# main_3_0.net
KiCad netlist of a schematic drawn in EAGLE
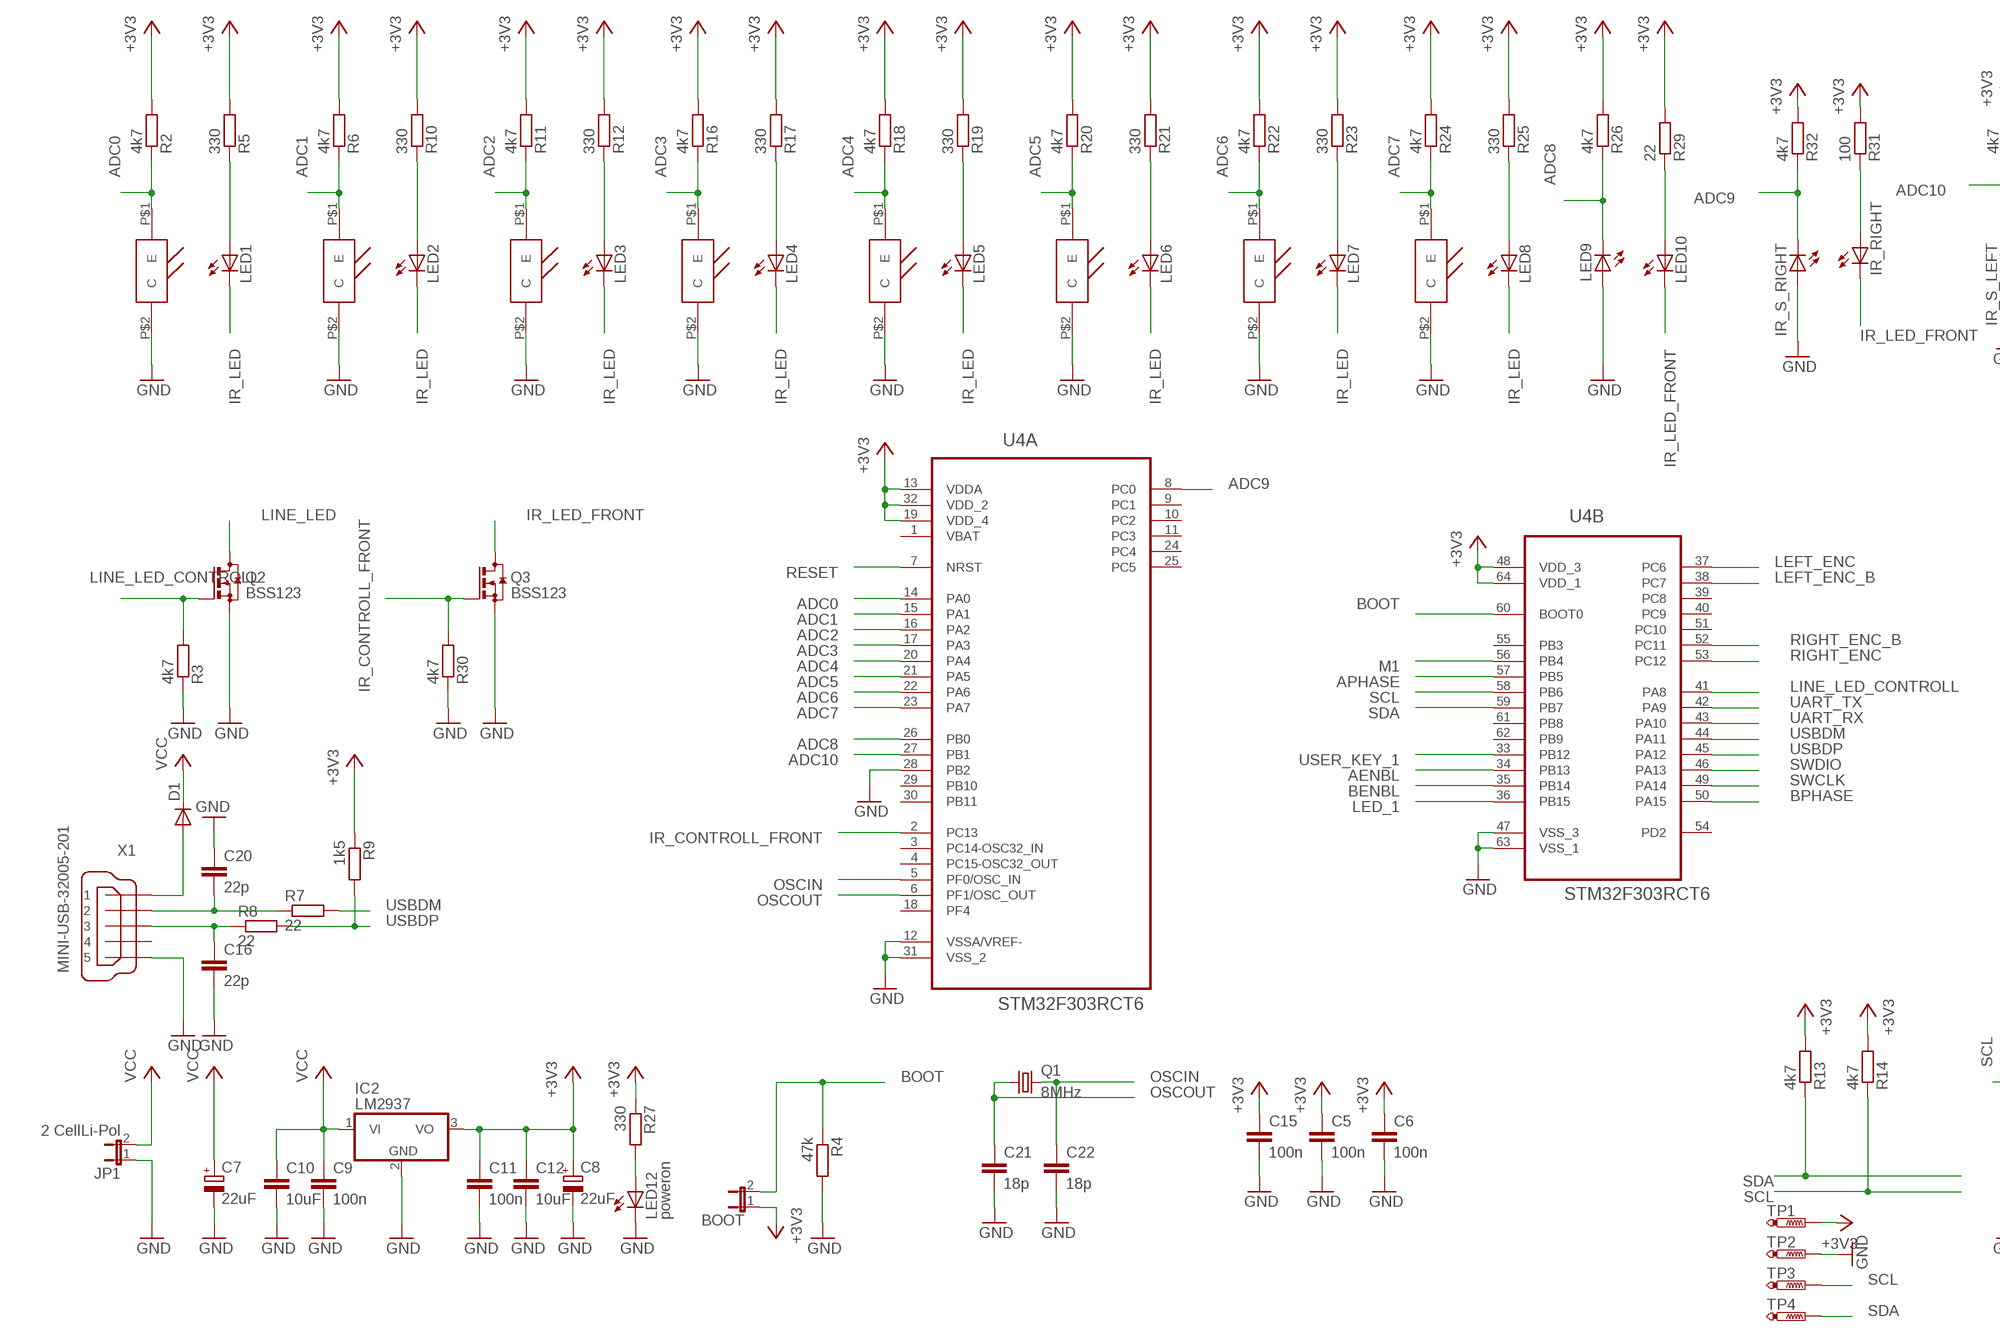
[diagram p0: schematic, sheet 1, part 1 of 2]
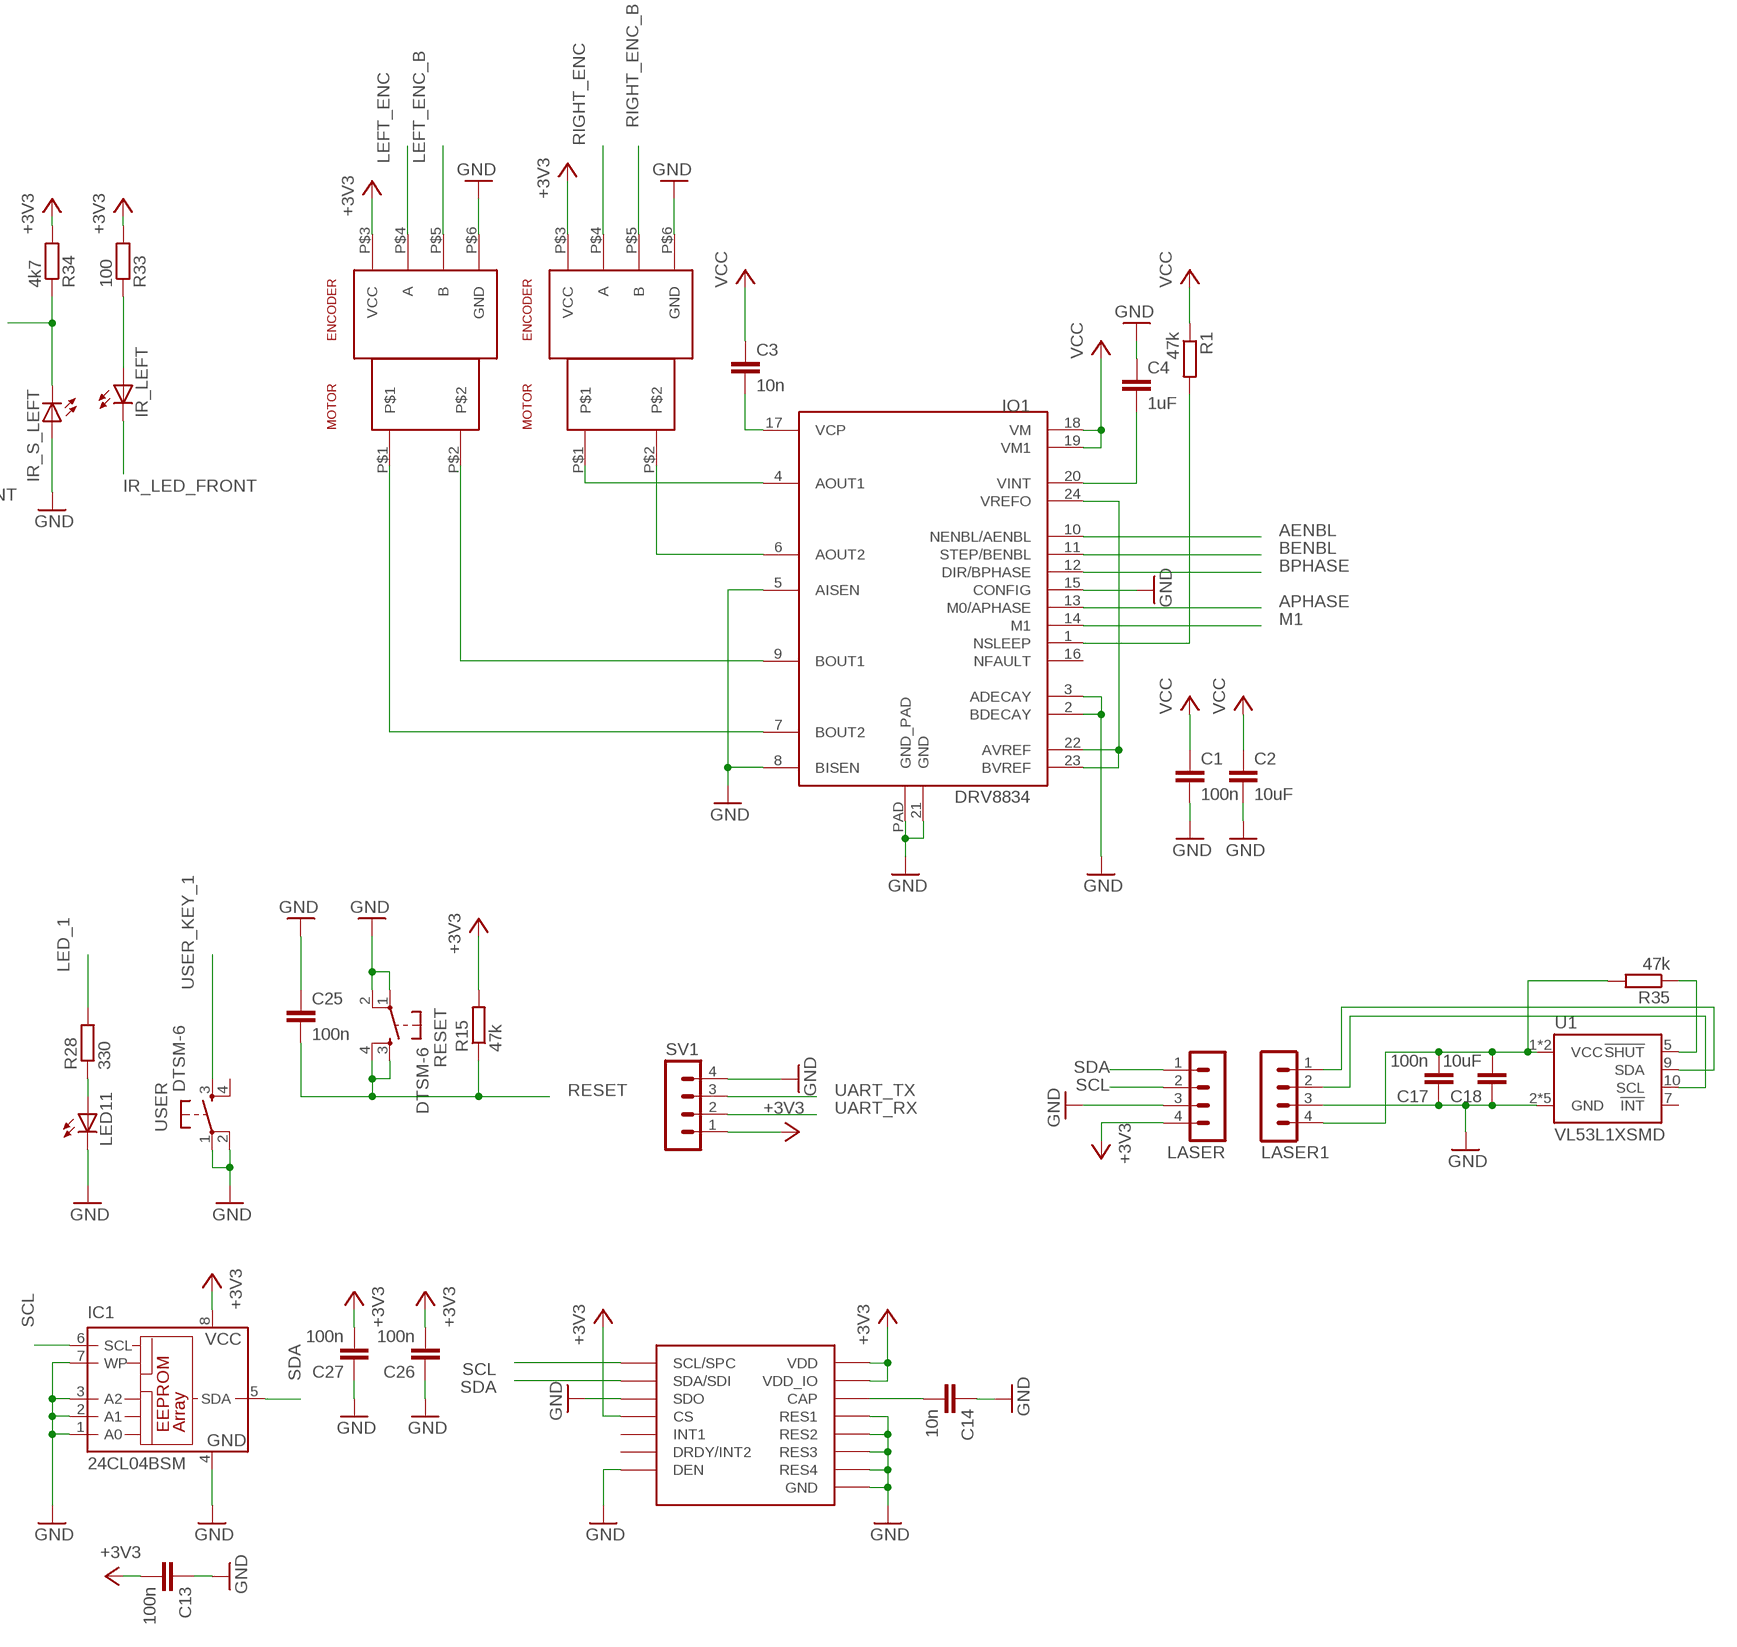
[diagram p1: schematic, sheet 1, part 2 of 2]

(export (version "E")
  (design (tool "Eeschema 10.0.6"))
  (components
    (comp (ref "BOOT")
      (value "JP1E")
      (footprint "eagle-import:JP1")
      (libsource (lib "eagle-import") (part "JP1E"))
    )
    (comp (ref "C1")
      (value "100n")
      (footprint "eagle-import:C1206")
      (libsource (lib "eagle-import") (part "C-EUC1206"))
    )
    (comp (ref "C2")
      (value "10uF")
      (footprint "eagle-import:C1206")
      (libsource (lib "eagle-import") (part "C-EUC1206"))
    )
    (comp (ref "C3")
      (value "10n")
      (footprint "eagle-import:C1206")
      (libsource (lib "eagle-import") (part "C-EUC1206"))
    )
    (comp (ref "C4")
      (value "1uF")
      (footprint "eagle-import:C1206")
      (libsource (lib "eagle-import") (part "C-EUC1206"))
    )
    (comp (ref "C5")
      (value "100n")
      (footprint "eagle-import:C0805")
      (libsource (lib "eagle-import") (part "C-EUC0805"))
    )
    (comp (ref "C6")
      (value "100n")
      (footprint "eagle-import:C0805")
      (libsource (lib "eagle-import") (part "C-EUC0805"))
    )
    (comp (ref "C7")
      (value "22uF")
      (footprint "eagle-import:153CLV-0505")
      (libsource (lib "eagle-import") (part "CPOL-EU153CLV-0505"))
    )
    (comp (ref "C8")
      (value "22uF")
      (footprint "eagle-import:153CLV-0505")
      (libsource (lib "eagle-import") (part "CPOL-EU153CLV-0505"))
    )
    (comp (ref "C9")
      (value "100n")
      (footprint "eagle-import:C0805")
      (libsource (lib "eagle-import") (part "C-EUC0805"))
    )
    (comp (ref "C10")
      (value "10uF")
      (footprint "eagle-import:C0805")
      (libsource (lib "eagle-import") (part "C-EUC0805"))
    )
    (comp (ref "C11")
      (value "100n")
      (footprint "eagle-import:C0805")
      (libsource (lib "eagle-import") (part "C-EUC0805"))
    )
    (comp (ref "C12")
      (value "10uF")
      (footprint "eagle-import:C0805")
      (libsource (lib "eagle-import") (part "C-EUC0805"))
    )
    (comp (ref "C13")
      (value "100n")
      (footprint "eagle-import:C0805")
      (libsource (lib "eagle-import") (part "C-EUC0805"))
    )
    (comp (ref "C14")
      (value "10n")
      (footprint "eagle-import:C0805")
      (libsource (lib "eagle-import") (part "C-EUC0805"))
    )
    (comp (ref "C15")
      (value "100n")
      (footprint "eagle-import:C0805")
      (libsource (lib "eagle-import") (part "C-EUC0805"))
    )
    (comp (ref "C16")
      (value "22p")
      (footprint "eagle-import:C0805")
      (libsource (lib "eagle-import") (part "C-EUC0805"))
    )
    (comp (ref "C17")
      (value "100n")
      (footprint "eagle-import:C0805")
      (libsource (lib "eagle-import") (part "C-EUC0805"))
    )
    (comp (ref "C18")
      (value "10uF")
      (footprint "eagle-import:C0805")
      (libsource (lib "eagle-import") (part "C-EUC0805"))
    )
    (comp (ref "C20")
      (value "22p")
      (footprint "eagle-import:C0805")
      (libsource (lib "eagle-import") (part "C-EUC0805"))
    )
    (comp (ref "C21")
      (value "18p")
      (footprint "eagle-import:C0805")
      (libsource (lib "eagle-import") (part "C-EUC0805"))
    )
    (comp (ref "C22")
      (value "18p")
      (footprint "eagle-import:C0805")
      (libsource (lib "eagle-import") (part "C-EUC0805"))
    )
    (comp (ref "C25")
      (value "100n")
      (footprint "eagle-import:C0805")
      (libsource (lib "eagle-import") (part "C-EUC0805"))
    )
    (comp (ref "C26")
      (value "100n")
      (footprint "eagle-import:C0805")
      (libsource (lib "eagle-import") (part "C-EUC0805"))
    )
    (comp (ref "C27")
      (value "100n")
      (footprint "eagle-import:C0805")
      (libsource (lib "eagle-import") (part "C-EUC0805"))
    )
    (comp (ref "D1")
      (value "DIODE-SMB")
      (footprint "eagle-import:SMB")
      (libsource (lib "eagle-import") (part "DIODE-SMB"))
    )
    (comp (ref "IC1")
      (value "24CL04BSM")
      (footprint "eagle-import:SO-08M")
      (fields (field (name "MPN") "FM24CL04-S"))
      (libsource (lib "eagle-import") (part "24SMCL04B"))
    )
    (comp (ref "IC2")
      (value "LM2937")
      (footprint "eagle-import:TO263-3")
      (libsource (lib "eagle-import") (part "LM2937"))
    )
    (comp (ref "IO1")
      (value "DRV8834")
      (footprint "eagle-import:DRV8834_PCK")
      (libsource (lib "eagle-import") (part "DRV8834"))
    )
    (comp (ref "IR_LEFT")
      (value "LED5MM")
      (footprint "eagle-import:LED5MM")
      (libsource (lib "eagle-import") (part "my_parts_LED5MM"))
    )
    (comp (ref "IR_RIGHT")
      (value "LED5MM")
      (footprint "eagle-import:LED5MM")
      (libsource (lib "eagle-import") (part "my_parts_LED5MM"))
    )
    (comp (ref "IR_S_LEFT")
      (value "LED5MM")
      (footprint "eagle-import:LED5MM")
      (libsource (lib "eagle-import") (part "my_parts_LED5MM"))
    )
    (comp (ref "IR_S_RIGHT")
      (value "LED5MM")
      (footprint "eagle-import:LED5MM")
      (libsource (lib "eagle-import") (part "my_parts_LED5MM"))
    )
    (comp (ref "JP1")
      (value "2 CellLi-Pol")
      (footprint "eagle-import:JP1")
      (libsource (lib "eagle-import") (part "JP1E"))
    )
    (comp (ref "LASER")
      (value "MA04-1")
      (footprint "eagle-import:MA04-1")
      (libsource (lib "eagle-import") (part "MA04-1"))
    )
    (comp (ref "LASER1")
      (value "MA04-1")
      (footprint "eagle-import:MA04-1")
      (libsource (lib "eagle-import") (part "MA04-1"))
    )
    (comp (ref "LED1")
      (value "LEDCHIPLED_1206")
      (footprint "eagle-import:CHIPLED_1206")
      (libsource (lib "eagle-import") (part "LEDCHIPLED_1206"))
    )
    (comp (ref "LED2")
      (value "LEDCHIPLED_1206")
      (footprint "eagle-import:CHIPLED_1206")
      (libsource (lib "eagle-import") (part "LEDCHIPLED_1206"))
    )
    (comp (ref "LED3")
      (value "LEDCHIPLED_1206")
      (footprint "eagle-import:CHIPLED_1206")
      (libsource (lib "eagle-import") (part "LEDCHIPLED_1206"))
    )
    (comp (ref "LED4")
      (value "LEDCHIPLED_1206")
      (footprint "eagle-import:CHIPLED_1206")
      (libsource (lib "eagle-import") (part "LEDCHIPLED_1206"))
    )
    (comp (ref "LED5")
      (value "LEDCHIPLED_1206")
      (footprint "eagle-import:CHIPLED_1206")
      (libsource (lib "eagle-import") (part "LEDCHIPLED_1206"))
    )
    (comp (ref "LED6")
      (value "LEDCHIPLED_1206")
      (footprint "eagle-import:CHIPLED_1206")
      (libsource (lib "eagle-import") (part "LEDCHIPLED_1206"))
    )
    (comp (ref "LED7")
      (value "LEDCHIPLED_1206")
      (footprint "eagle-import:CHIPLED_1206")
      (libsource (lib "eagle-import") (part "LEDCHIPLED_1206"))
    )
    (comp (ref "LED8")
      (value "LEDCHIPLED_1206")
      (footprint "eagle-import:CHIPLED_1206")
      (libsource (lib "eagle-import") (part "LEDCHIPLED_1206"))
    )
    (comp (ref "LED9")
      (value "LED5MM")
      (footprint "eagle-import:LED5MM")
      (libsource (lib "eagle-import") (part "my_parts_LED5MM"))
    )
    (comp (ref "LED10")
      (value "LED5MM")
      (footprint "eagle-import:LED5MM")
      (libsource (lib "eagle-import") (part "my_parts_LED5MM"))
    )
    (comp (ref "LED11")
      (value "LEDCHIPLED_1206")
      (footprint "eagle-import:CHIPLED_1206")
      (libsource (lib "eagle-import") (part "LEDCHIPLED_1206"))
    )
    (comp (ref "LED12")
      (value "poweron")
      (footprint "eagle-import:CHIPLED_1206")
      (libsource (lib "eagle-import") (part "LEDCHIPLED_1206"))
    )
    (comp (ref "LSM6DS0")
      (value "L3GD20H")
      (footprint "eagle-import:LGA16L")
      (libsource (lib "eagle-import") (part "L3GD20H"))
    )
    (comp (ref "Q1")
      (value "8MHz")
      (footprint "eagle-import:CTS406")
      (libsource (lib "eagle-import") (part "CRYSTALCTS406"))
    )
    (comp (ref "Q2")
      (value "BSS123")
      (footprint "eagle-import:SOT23")
      (libsource (lib "eagle-import") (part "BSS123"))
    )
    (comp (ref "Q3")
      (value "BSS123")
      (footprint "eagle-import:SOT23")
      (libsource (lib "eagle-import") (part "BSS123"))
    )
    (comp (ref "R1")
      (value "47k")
      (footprint "eagle-import:M1206")
      (libsource (lib "eagle-import") (part "R-EU_M1206"))
    )
    (comp (ref "R2")
      (value "4k7")
      (footprint "eagle-import:M0805")
      (libsource (lib "eagle-import") (part "R-EU_M0805"))
    )
    (comp (ref "R3")
      (value "4k7")
      (footprint "eagle-import:M0805")
      (libsource (lib "eagle-import") (part "R-EU_M0805"))
    )
    (comp (ref "R4")
      (value "47k")
      (footprint "eagle-import:M0805")
      (libsource (lib "eagle-import") (part "R-EU_M0805"))
    )
    (comp (ref "R5")
      (value "330")
      (footprint "eagle-import:M0805")
      (libsource (lib "eagle-import") (part "R-EU_M0805"))
    )
    (comp (ref "R6")
      (value "4k7")
      (footprint "eagle-import:M0805")
      (libsource (lib "eagle-import") (part "R-EU_M0805"))
    )
    (comp (ref "R7")
      (value "22")
      (footprint "eagle-import:M0805")
      (libsource (lib "eagle-import") (part "R-EU_M0805"))
    )
    (comp (ref "R8")
      (value "22")
      (footprint "eagle-import:M0805")
      (libsource (lib "eagle-import") (part "R-EU_M0805"))
    )
    (comp (ref "R9")
      (value "1k5")
      (footprint "eagle-import:M0805")
      (libsource (lib "eagle-import") (part "R-EU_M0805"))
    )
    (comp (ref "R10")
      (value "330")
      (footprint "eagle-import:M0805")
      (libsource (lib "eagle-import") (part "R-EU_M0805"))
    )
    (comp (ref "R11")
      (value "4k7")
      (footprint "eagle-import:M0805")
      (libsource (lib "eagle-import") (part "R-EU_M0805"))
    )
    (comp (ref "R12")
      (value "330")
      (footprint "eagle-import:M0805")
      (libsource (lib "eagle-import") (part "R-EU_M0805"))
    )
    (comp (ref "R13")
      (value "4k7")
      (footprint "eagle-import:M0805")
      (libsource (lib "eagle-import") (part "R-EU_M0805"))
    )
    (comp (ref "R14")
      (value "4k7")
      (footprint "eagle-import:M0805")
      (libsource (lib "eagle-import") (part "R-EU_M0805"))
    )
    (comp (ref "R15")
      (value "47k")
      (footprint "eagle-import:M0805")
      (libsource (lib "eagle-import") (part "R-EU_M0805"))
    )
    (comp (ref "R16")
      (value "4k7")
      (footprint "eagle-import:M0805")
      (libsource (lib "eagle-import") (part "R-EU_M0805"))
    )
    (comp (ref "R17")
      (value "330")
      (footprint "eagle-import:M0805")
      (libsource (lib "eagle-import") (part "R-EU_M0805"))
    )
    (comp (ref "R18")
      (value "4k7")
      (footprint "eagle-import:M0805")
      (libsource (lib "eagle-import") (part "R-EU_M0805"))
    )
    (comp (ref "R19")
      (value "330")
      (footprint "eagle-import:M0805")
      (libsource (lib "eagle-import") (part "R-EU_M0805"))
    )
    (comp (ref "R20")
      (value "4k7")
      (footprint "eagle-import:M0805")
      (libsource (lib "eagle-import") (part "R-EU_M0805"))
    )
    (comp (ref "R21")
      (value "330")
      (footprint "eagle-import:M0805")
      (libsource (lib "eagle-import") (part "R-EU_M0805"))
    )
    (comp (ref "R22")
      (value "4k7")
      (footprint "eagle-import:M0805")
      (libsource (lib "eagle-import") (part "R-EU_M0805"))
    )
    (comp (ref "R23")
      (value "330")
      (footprint "eagle-import:M0805")
      (libsource (lib "eagle-import") (part "R-EU_M0805"))
    )
    (comp (ref "R24")
      (value "4k7")
      (footprint "eagle-import:M0805")
      (libsource (lib "eagle-import") (part "R-EU_M0805"))
    )
    (comp (ref "R25")
      (value "330")
      (footprint "eagle-import:M0805")
      (libsource (lib "eagle-import") (part "R-EU_M0805"))
    )
    (comp (ref "R26")
      (value "4k7")
      (footprint "eagle-import:M0805")
      (libsource (lib "eagle-import") (part "R-EU_M0805"))
    )
    (comp (ref "R27")
      (value "330")
      (footprint "eagle-import:M0805")
      (libsource (lib "eagle-import") (part "R-EU_M0805"))
    )
    (comp (ref "R28")
      (value "330")
      (footprint "eagle-import:M0805")
      (libsource (lib "eagle-import") (part "R-EU_M0805"))
    )
    (comp (ref "R29")
      (value "22")
      (footprint "eagle-import:M0805")
      (libsource (lib "eagle-import") (part "R-EU_M0805"))
    )
    (comp (ref "R30")
      (value "4k7")
      (footprint "eagle-import:M0805")
      (libsource (lib "eagle-import") (part "R-EU_M0805"))
    )
    (comp (ref "R31")
      (value "100")
      (footprint "eagle-import:M0805")
      (libsource (lib "eagle-import") (part "R-EU_M0805"))
    )
    (comp (ref "R32")
      (value "4k7")
      (footprint "eagle-import:M0805")
      (libsource (lib "eagle-import") (part "R-EU_M0805"))
    )
    (comp (ref "R33")
      (value "100")
      (footprint "eagle-import:M0805")
      (libsource (lib "eagle-import") (part "R-EU_M0805"))
    )
    (comp (ref "R34")
      (value "4k7")
      (footprint "eagle-import:M0805")
      (libsource (lib "eagle-import") (part "R-EU_M0805"))
    )
    (comp (ref "R35")
      (value "47k")
      (footprint "eagle-import:M0805")
      (libsource (lib "eagle-import") (part "R-EU_M0805"))
    )
    (comp (ref "RESET")
      (value "DTSM-6")
      (footprint "eagle-import:DTSM-6")
      (libsource (lib "eagle-import") (part "DTSM-6"))
    )
    (comp (ref "SV1")
      (value "MA04-1")
      (footprint "eagle-import:MA04-1")
      (libsource (lib "eagle-import") (part "MA04-1"))
    )
    (comp (ref "TP1")
      (value "PTR1B1,27")
      (footprint "eagle-import:B1,27")
      (libsource (lib "eagle-import") (part "PTR1B1,27"))
    )
    (comp (ref "TP2")
      (value "PTR1B1,27")
      (footprint "eagle-import:B1,27")
      (libsource (lib "eagle-import") (part "PTR1B1,27"))
    )
    (comp (ref "TP3")
      (value "PTR1B1,27")
      (footprint "eagle-import:B1,27")
      (libsource (lib "eagle-import") (part "PTR1B1,27"))
    )
    (comp (ref "TP4")
      (value "PTR1B1,27")
      (footprint "eagle-import:B1,27")
      (libsource (lib "eagle-import") (part "PTR1B1,27"))
    )
    (comp (ref "U$3")
      (value "SFH3710")
      (footprint "eagle-import:SFH3710")
      (libsource (lib "eagle-import") (part "SFH3710"))
    )
    (comp (ref "U$4")
      (value "SFH3710")
      (footprint "eagle-import:SFH3710")
      (libsource (lib "eagle-import") (part "SFH3710"))
    )
    (comp (ref "U$5")
      (value "SFH3710")
      (footprint "eagle-import:SFH3710")
      (libsource (lib "eagle-import") (part "SFH3710"))
    )
    (comp (ref "U$6")
      (value "SFH3710")
      (footprint "eagle-import:SFH3710")
      (libsource (lib "eagle-import") (part "SFH3710"))
    )
    (comp (ref "U$7")
      (value "SFH3710")
      (footprint "eagle-import:SFH3710")
      (libsource (lib "eagle-import") (part "SFH3710"))
    )
    (comp (ref "U$8")
      (value "SFH3710")
      (footprint "eagle-import:SFH3710")
      (libsource (lib "eagle-import") (part "SFH3710"))
    )
    (comp (ref "U$9")
      (value "SFH3710")
      (footprint "eagle-import:SFH3710")
      (libsource (lib "eagle-import") (part "SFH3710"))
    )
    (comp (ref "U$10")
      (value "SFH3710")
      (footprint "eagle-import:SFH3710")
      (libsource (lib "eagle-import") (part "SFH3710"))
    )
    (comp (ref "U$11")
      (value "POLOLU_GEAR_MOTORPOLO")
      (footprint "eagle-import:POLOLU_GEAR_MOTOR")
      (libsource (lib "eagle-import") (part "POLOLU_GEAR_MOTORPOLO"))
    )
    (comp (ref "U$12")
      (value "POLOLU_GEAR_MOTORPOLO")
      (footprint "eagle-import:POLOLU_GEAR_MOTOR")
      (libsource (lib "eagle-import") (part "POLOLU_GEAR_MOTORPOLO"))
    )
    (comp (ref "U1")
      (value "VL53L1XSMD")
      (footprint "eagle-import:VL53L1X")
      (libsource (lib "eagle-import") (part "VL53L1XSMD"))
    )
    (comp (ref "U4")
      (value "STM32F303RCT6")
      (footprint "eagle-import:QFP50P1200X1200X160-64N")
      (libsource (lib "eagle-import") (part "STM32F303RCT6"))
    )
    (comp (ref "USER")
      (value "DTSM-6")
      (footprint "eagle-import:DTSM-6")
      (libsource (lib "eagle-import") (part "DTSM-6"))
    )
    (comp (ref "X1")
      (value "MINI-USB-32005-201")
      (footprint "eagle-import:32005-201")
      (libsource (lib "eagle-import") (part "MINI-USB-32005-201"))
    )
  )
  (nets
    (net (code "1") (name "+3V3") (class "Default")
      (node (ref "BOOT") (pin "1") (pinfunction "1_1") (pintype "passive"))
      (node (ref "C11") (pin "1") (pinfunction "1_1") (pintype "passive"))
      (node (ref "C12") (pin "1") (pinfunction "1_1") (pintype "passive"))
      (node (ref "C13") (pin "2") (pinfunction "2_2") (pintype "passive"))
      (node (ref "C15") (pin "1") (pinfunction "1_1") (pintype "passive"))
      (node (ref "C26") (pin "2") (pinfunction "2_2") (pintype "passive"))
      (node (ref "C27") (pin "2") (pinfunction "2_2") (pintype "passive"))
      (node (ref "C5") (pin "1") (pinfunction "1_1") (pintype "passive"))
      (node (ref "C6") (pin "1") (pinfunction "1_1") (pintype "passive"))
      (node (ref "C8") (pin "+") (pinfunction "+_+") (pintype "passive"))
      (node (ref "IC1") (pin "8") (pinfunction "VCC_8") (pintype "power_in"))
      (node (ref "IC2") (pin "3") (pinfunction "VO_3") (pintype "passive"))
      (node (ref "LASER") (pin "4") (pinfunction "4_4") (pintype "passive"))
      (node (ref "LSM6DS0") (pin "P$1") (pinfunction "VDD_IO_P$1") (pintype "power_in"))
      (node (ref "LSM6DS0") (pin "P$16") (pinfunction "VDD_P$16") (pintype "power_in"))
      (node (ref "LSM6DS0") (pin "P$5") (pinfunction "CS_P$5") (pintype "bidirectional"))
      (node (ref "R10") (pin "2") (pinfunction "2_2") (pintype "passive"))
      (node (ref "R11") (pin "2") (pinfunction "2_2") (pintype "passive"))
      (node (ref "R12") (pin "2") (pinfunction "2_2") (pintype "passive"))
      (node (ref "R13") (pin "2") (pinfunction "2_2") (pintype "passive"))
      (node (ref "R14") (pin "2") (pinfunction "2_2") (pintype "passive"))
      (node (ref "R15") (pin "2") (pinfunction "2_2") (pintype "passive"))
      (node (ref "R16") (pin "2") (pinfunction "2_2") (pintype "passive"))
      (node (ref "R17") (pin "2") (pinfunction "2_2") (pintype "passive"))
      (node (ref "R18") (pin "2") (pinfunction "2_2") (pintype "passive"))
      (node (ref "R19") (pin "2") (pinfunction "2_2") (pintype "passive"))
      (node (ref "R2") (pin "2") (pinfunction "2_2") (pintype "passive"))
      (node (ref "R20") (pin "2") (pinfunction "2_2") (pintype "passive"))
      (node (ref "R21") (pin "2") (pinfunction "2_2") (pintype "passive"))
      (node (ref "R22") (pin "2") (pinfunction "2_2") (pintype "passive"))
      (node (ref "R23") (pin "2") (pinfunction "2_2") (pintype "passive"))
      (node (ref "R24") (pin "2") (pinfunction "2_2") (pintype "passive"))
      (node (ref "R25") (pin "2") (pinfunction "2_2") (pintype "passive"))
      (node (ref "R26") (pin "2") (pinfunction "2_2") (pintype "passive"))
      (node (ref "R27") (pin "1") (pinfunction "1_1") (pintype "passive"))
      (node (ref "R29") (pin "2") (pinfunction "2_2") (pintype "passive"))
      (node (ref "R31") (pin "2") (pinfunction "2_2") (pintype "passive"))
      (node (ref "R32") (pin "2") (pinfunction "2_2") (pintype "passive"))
      (node (ref "R33") (pin "2") (pinfunction "2_2") (pintype "passive"))
      (node (ref "R34") (pin "2") (pinfunction "2_2") (pintype "passive"))
      (node (ref "R5") (pin "2") (pinfunction "2_2") (pintype "passive"))
      (node (ref "R6") (pin "2") (pinfunction "2_2") (pintype "passive"))
      (node (ref "R9") (pin "1") (pinfunction "1_1") (pintype "passive"))
      (node (ref "SV1") (pin "1") (pinfunction "1_1") (pintype "passive"))
      (node (ref "TP1") (pin "TP") (pinfunction "TP_TP") (pintype "input"))
      (node (ref "U$11") (pin "P$3") (pinfunction "VCC_P$3") (pintype "bidirectional"))
      (node (ref "U$12") (pin "P$3") (pinfunction "VCC_P$3") (pintype "bidirectional"))
      (node (ref "U4") (pin "13") (pinfunction "VDDA_13") (pintype "power_in"))
      (node (ref "U4") (pin "19") (pinfunction "VDD_4_19") (pintype "power_in"))
      (node (ref "U4") (pin "32") (pinfunction "VDD_2_32") (pintype "power_in"))
      (node (ref "U4") (pin "48") (pinfunction "VDD_3_48") (pintype "power_in"))
      (node (ref "U4") (pin "64") (pinfunction "VDD_1_64") (pintype "power_in"))
    )
    (net (code "2") (name "/ADC0") (class "Default")
      (node (ref "R2") (pin "1") (pinfunction "1_1") (pintype "passive"))
      (node (ref "U$3") (pin "P$1") (pinfunction "E_P$1") (pintype "bidirectional"))
      (node (ref "U4") (pin "14") (pinfunction "PA0_14") (pintype "bidirectional"))
    )
    (net (code "3") (name "/ADC1") (class "Default")
      (node (ref "R6") (pin "1") (pinfunction "1_1") (pintype "passive"))
      (node (ref "U$4") (pin "P$1") (pinfunction "E_P$1") (pintype "bidirectional"))
      (node (ref "U4") (pin "15") (pinfunction "PA1_15") (pintype "bidirectional"))
    )
    (net (code "4") (name "/ADC2") (class "Default")
      (node (ref "R11") (pin "1") (pinfunction "1_1") (pintype "passive"))
      (node (ref "U$5") (pin "P$1") (pinfunction "E_P$1") (pintype "bidirectional"))
      (node (ref "U4") (pin "16") (pinfunction "PA2_16") (pintype "bidirectional"))
    )
    (net (code "5") (name "/ADC3") (class "Default")
      (node (ref "R16") (pin "1") (pinfunction "1_1") (pintype "passive"))
      (node (ref "U$6") (pin "P$1") (pinfunction "E_P$1") (pintype "bidirectional"))
      (node (ref "U4") (pin "17") (pinfunction "PA3_17") (pintype "bidirectional"))
    )
    (net (code "6") (name "/ADC4") (class "Default")
      (node (ref "R18") (pin "1") (pinfunction "1_1") (pintype "passive"))
      (node (ref "U$7") (pin "P$1") (pinfunction "E_P$1") (pintype "bidirectional"))
      (node (ref "U4") (pin "20") (pinfunction "PA4_20") (pintype "bidirectional"))
    )
    (net (code "7") (name "/ADC5") (class "Default")
      (node (ref "R20") (pin "1") (pinfunction "1_1") (pintype "passive"))
      (node (ref "U$8") (pin "P$1") (pinfunction "E_P$1") (pintype "bidirectional"))
      (node (ref "U4") (pin "21") (pinfunction "PA5_21") (pintype "bidirectional"))
    )
    (net (code "8") (name "/ADC6") (class "Default")
      (node (ref "R22") (pin "1") (pinfunction "1_1") (pintype "passive"))
      (node (ref "U$9") (pin "P$1") (pinfunction "E_P$1") (pintype "bidirectional"))
      (node (ref "U4") (pin "22") (pinfunction "PA6_22") (pintype "bidirectional"))
    )
    (net (code "9") (name "/ADC7") (class "Default")
      (node (ref "R24") (pin "1") (pinfunction "1_1") (pintype "passive"))
      (node (ref "U$10") (pin "P$1") (pinfunction "E_P$1") (pintype "bidirectional"))
      (node (ref "U4") (pin "23") (pinfunction "PA7_23") (pintype "bidirectional"))
    )
    (net (code "10") (name "/ADC8") (class "Default")
      (node (ref "LED9") (pin "K") (pinfunction "C_K") (pintype "passive"))
      (node (ref "R26") (pin "1") (pinfunction "1_1") (pintype "passive"))
      (node (ref "U4") (pin "26") (pinfunction "PB0_26") (pintype "bidirectional"))
    )
    (net (code "11") (name "/ADC9") (class "Default")
      (node (ref "IR_S_RIGHT") (pin "K") (pinfunction "C_K") (pintype "passive"))
      (node (ref "R32") (pin "1") (pinfunction "1_1") (pintype "passive"))
      (node (ref "U4") (pin "8") (pinfunction "PC0_8") (pintype "bidirectional"))
    )
    (net (code "12") (name "/ADC10") (class "Default")
      (node (ref "IR_S_LEFT") (pin "K") (pinfunction "C_K") (pintype "passive"))
      (node (ref "R34") (pin "1") (pinfunction "1_1") (pintype "passive"))
      (node (ref "U4") (pin "27") (pinfunction "PB1_27") (pintype "bidirectional"))
    )
    (net (code "13") (name "/AENBL") (class "Default")
      (node (ref "IO1") (pin "10") (pinfunction "NENBL/AENBL_10") (pintype "bidirectional"))
      (node (ref "U4") (pin "34") (pinfunction "PB13_34") (pintype "bidirectional"))
    )
    (net (code "14") (name "/APHASE") (class "Default")
      (node (ref "IO1") (pin "13") (pinfunction "M0/APHASE_13") (pintype "bidirectional"))
      (node (ref "U4") (pin "57") (pinfunction "PB5_57") (pintype "bidirectional"))
    )
    (net (code "15") (name "/BENBL") (class "Default")
      (node (ref "IO1") (pin "11") (pinfunction "STEP/BENBL_11") (pintype "bidirectional"))
      (node (ref "U4") (pin "35") (pinfunction "PB14_35") (pintype "bidirectional"))
    )
    (net (code "16") (name "/BOOT") (class "Default")
      (node (ref "BOOT") (pin "2") (pinfunction "2_2") (pintype "passive"))
      (node (ref "R4") (pin "1") (pinfunction "1_1") (pintype "passive"))
      (node (ref "U4") (pin "60") (pinfunction "BOOT0_60") (pintype "input"))
    )
    (net (code "17") (name "/BPHASE") (class "Default")
      (node (ref "IO1") (pin "12") (pinfunction "DIR/BPHASE_12") (pintype "bidirectional"))
      (node (ref "U4") (pin "50") (pinfunction "PA15_50") (pintype "bidirectional"))
    )
    (net (code "18") (name "/IR_CONTROLL_FRONT") (class "Default")
      (node (ref "Q3") (pin "1") (pinfunction "G_1") (pintype "passive"))
      (node (ref "R30") (pin "2") (pinfunction "2_2") (pintype "passive"))
      (node (ref "U4") (pin "2") (pinfunction "PC13_2") (pintype "bidirectional"))
    )
    (net (code "19") (name "/IR_LED") (class "Default")
      (node (ref "LED1") (pin "C") (pinfunction "C_C") (pintype "passive"))
      (node (ref "LED2") (pin "C") (pinfunction "C_C") (pintype "passive"))
      (node (ref "LED3") (pin "C") (pinfunction "C_C") (pintype "passive"))
      (node (ref "LED4") (pin "C") (pinfunction "C_C") (pintype "passive"))
      (node (ref "LED5") (pin "C") (pinfunction "C_C") (pintype "passive"))
      (node (ref "LED6") (pin "C") (pinfunction "C_C") (pintype "passive"))
      (node (ref "LED7") (pin "C") (pinfunction "C_C") (pintype "passive"))
      (node (ref "LED8") (pin "C") (pinfunction "C_C") (pintype "passive"))
    )
    (net (code "20") (name "/IR_LED_FRONT") (class "Default")
      (node (ref "IR_LEFT") (pin "K") (pinfunction "C_K") (pintype "passive"))
      (node (ref "IR_RIGHT") (pin "K") (pinfunction "C_K") (pintype "passive"))
      (node (ref "LED10") (pin "K") (pinfunction "C_K") (pintype "passive"))
      (node (ref "Q3") (pin "3") (pinfunction "D_3") (pintype "passive"))
    )
    (net (code "21") (name "/LED_1") (class "Default")
      (node (ref "R28") (pin "2") (pinfunction "2_2") (pintype "passive"))
      (node (ref "U4") (pin "36") (pinfunction "PB15_36") (pintype "bidirectional"))
    )
    (net (code "22") (name "/LEFT_ENC") (class "Default")
      (node (ref "U$11") (pin "P$4") (pinfunction "A_P$4") (pintype "bidirectional"))
      (node (ref "U4") (pin "37") (pinfunction "PC6_37") (pintype "bidirectional"))
    )
    (net (code "23") (name "/LEFT_ENC_B") (class "Default")
      (node (ref "U$11") (pin "P$5") (pinfunction "B_P$5") (pintype "bidirectional"))
      (node (ref "U4") (pin "38") (pinfunction "PC7_38") (pintype "bidirectional"))
    )
    (net (code "24") (name "/LINE_LED") (class "Default")
      (node (ref "Q2") (pin "3") (pinfunction "D_3") (pintype "passive"))
    )
    (net (code "25") (name "/LINE_LED_CONTROLL") (class "Default")
      (node (ref "Q2") (pin "1") (pinfunction "G_1") (pintype "passive"))
      (node (ref "R3") (pin "2") (pinfunction "2_2") (pintype "passive"))
      (node (ref "U4") (pin "41") (pinfunction "PA8_41") (pintype "bidirectional"))
    )
    (net (code "26") (name "/M1") (class "Default")
      (node (ref "IO1") (pin "14") (pinfunction "M1_14") (pintype "bidirectional"))
      (node (ref "U4") (pin "56") (pinfunction "PB4_56") (pintype "bidirectional"))
    )
    (net (code "27") (name "/OSCIN") (class "Default")
      (node (ref "C22") (pin "1") (pinfunction "1_1") (pintype "passive"))
      (node (ref "Q1") (pin "3") (pinfunction "2_3") (pintype "passive"))
      (node (ref "U4") (pin "5") (pinfunction "PF0/OSC_IN_5") (pintype "bidirectional"))
    )
    (net (code "28") (name "/OSCOUT") (class "Default")
      (node (ref "C21") (pin "1") (pinfunction "1_1") (pintype "passive"))
      (node (ref "Q1") (pin "1") (pinfunction "1_1") (pintype "passive"))
      (node (ref "U4") (pin "6") (pinfunction "PF1/OSC_OUT_6") (pintype "bidirectional"))
    )
    (net (code "29") (name "/RESET") (class "Default")
      (node (ref "C25") (pin "2") (pinfunction "2_2") (pintype "passive"))
      (node (ref "R15") (pin "1") (pinfunction "1_1") (pintype "passive"))
      (node (ref "RESET") (pin "3") (pinfunction "3_3") (pintype "passive"))
      (node (ref "RESET") (pin "4") (pinfunction "4_4") (pintype "passive"))
      (node (ref "U4") (pin "7") (pinfunction "NRST_7") (pintype "bidirectional"))
    )
    (net (code "30") (name "/RIGHT_ENC") (class "Default")
      (node (ref "U$12") (pin "P$4") (pinfunction "A_P$4") (pintype "bidirectional"))
      (node (ref "U4") (pin "53") (pinfunction "PC12_53") (pintype "bidirectional"))
    )
    (net (code "31") (name "/RIGHT_ENC_B") (class "Default")
      (node (ref "U$12") (pin "P$5") (pinfunction "B_P$5") (pintype "bidirectional"))
      (node (ref "U4") (pin "52") (pinfunction "PC11_52") (pintype "bidirectional"))
    )
    (net (code "32") (name "/SCL") (class "Default")
      (node (ref "IC1") (pin "6") (pinfunction "SCL_6") (pintype "input"))
      (node (ref "LASER") (pin "2") (pinfunction "2_2") (pintype "passive"))
      (node (ref "LSM6DS0") (pin "P$2") (pinfunction "SCL/SPC_P$2") (pintype "bidirectional"))
      (node (ref "R14") (pin "1") (pinfunction "1_1") (pintype "passive"))
      (node (ref "TP3") (pin "TP") (pinfunction "TP_TP") (pintype "input"))
      (node (ref "U4") (pin "58") (pinfunction "PB6_58") (pintype "bidirectional"))
    )
    (net (code "33") (name "/SDA") (class "Default")
      (node (ref "IC1") (pin "5") (pinfunction "SDA_5") (pintype "bidirectional"))
      (node (ref "LASER") (pin "1") (pinfunction "1_1") (pintype "passive"))
      (node (ref "LSM6DS0") (pin "P$3") (pinfunction "SDA/SDI_P$3") (pintype "bidirectional"))
      (node (ref "R13") (pin "1") (pinfunction "1_1") (pintype "passive"))
      (node (ref "TP4") (pin "TP") (pinfunction "TP_TP") (pintype "input"))
      (node (ref "U4") (pin "59") (pinfunction "PB7_59") (pintype "bidirectional"))
    )
    (net (code "34") (name "/SWCLK") (class "Default")
      (node (ref "U4") (pin "49") (pinfunction "PA14_49") (pintype "bidirectional"))
    )
    (net (code "35") (name "/SWDIO") (class "Default")
      (node (ref "U4") (pin "46") (pinfunction "PA13_46") (pintype "bidirectional"))
    )
    (net (code "36") (name "/UART_RX") (class "Default")
      (node (ref "SV1") (pin "2") (pinfunction "2_2") (pintype "passive"))
      (node (ref "U4") (pin "43") (pinfunction "PA10_43") (pintype "bidirectional"))
    )
    (net (code "37") (name "/UART_TX") (class "Default")
      (node (ref "SV1") (pin "3") (pinfunction "3_3") (pintype "passive"))
      (node (ref "U4") (pin "42") (pinfunction "PA9_42") (pintype "bidirectional"))
    )
    (net (code "38") (name "/USBDM") (class "Default")
      (node (ref "R7") (pin "2") (pinfunction "2_2") (pintype "passive"))
      (node (ref "U4") (pin "44") (pinfunction "PA11_44") (pintype "bidirectional"))
    )
    (net (code "39") (name "/USBDP") (class "Default")
      (node (ref "R8") (pin "2") (pinfunction "2_2") (pintype "passive"))
      (node (ref "R9") (pin "2") (pinfunction "2_2") (pintype "passive"))
      (node (ref "U4") (pin "45") (pinfunction "PA12_45") (pintype "bidirectional"))
    )
    (net (code "40") (name "/USER_KEY_1") (class "Default")
      (node (ref "U4") (pin "33") (pinfunction "PB12_33") (pintype "bidirectional"))
      (node (ref "USER") (pin "3") (pinfunction "3_3") (pintype "passive"))
    )
    (net (code "41") (name "/VBAT") (class "Default")
      (node (ref "U4") (pin "1") (pinfunction "VBAT_1") (pintype "power_in"))
    )
    (net (code "42") (name "GND") (class "Default")
      (node (ref "C1") (pin "2") (pinfunction "2_2") (pintype "passive"))
      (node (ref "C10") (pin "2") (pinfunction "2_2") (pintype "passive"))
      (node (ref "C11") (pin "2") (pinfunction "2_2") (pintype "passive"))
      (node (ref "C12") (pin "2") (pinfunction "2_2") (pintype "passive"))
      (node (ref "C13") (pin "1") (pinfunction "1_1") (pintype "passive"))
      (node (ref "C14") (pin "1") (pinfunction "1_1") (pintype "passive"))
      (node (ref "C15") (pin "2") (pinfunction "2_2") (pintype "passive"))
      (node (ref "C16") (pin "2") (pinfunction "2_2") (pintype "passive"))
      (node (ref "C17") (pin "1") (pinfunction "1_1") (pintype "passive"))
      (node (ref "C18") (pin "1") (pinfunction "1_1") (pintype "passive"))
      (node (ref "C2") (pin "2") (pinfunction "2_2") (pintype "passive"))
      (node (ref "C20") (pin "1") (pinfunction "1_1") (pintype "passive"))
      (node (ref "C21") (pin "2") (pinfunction "2_2") (pintype "passive"))
      (node (ref "C22") (pin "2") (pinfunction "2_2") (pintype "passive"))
      (node (ref "C25") (pin "1") (pinfunction "1_1") (pintype "passive"))
      (node (ref "C26") (pin "1") (pinfunction "1_1") (pintype "passive"))
      (node (ref "C27") (pin "1") (pinfunction "1_1") (pintype "passive"))
      (node (ref "C4") (pin "1") (pinfunction "1_1") (pintype "passive"))
      (node (ref "C5") (pin "2") (pinfunction "2_2") (pintype "passive"))
      (node (ref "C6") (pin "2") (pinfunction "2_2") (pintype "passive"))
      (node (ref "C7") (pin "-") (pinfunction "-_-") (pintype "passive"))
      (node (ref "C8") (pin "-") (pinfunction "-_-") (pintype "passive"))
      (node (ref "C9") (pin "2") (pinfunction "2_2") (pintype "passive"))
      (node (ref "IC1") (pin "1") (pinfunction "A0_1") (pintype "input"))
      (node (ref "IC1") (pin "2") (pinfunction "A1_2") (pintype "input"))
      (node (ref "IC1") (pin "3") (pinfunction "A2_3") (pintype "input"))
      (node (ref "IC1") (pin "4") (pinfunction "GND_4") (pintype "power_in"))
      (node (ref "IC1") (pin "7") (pinfunction "WP_7") (pintype "input"))
      (node (ref "IC2") (pin "2") (pinfunction "GND_2") (pintype "passive"))
      (node (ref "IO1") (pin "15") (pinfunction "CONFIG_15") (pintype "bidirectional"))
      (node (ref "IO1") (pin "2") (pinfunction "BDECAY_2") (pintype "bidirectional"))
      (node (ref "IO1") (pin "21") (pinfunction "GND_21") (pintype "bidirectional"))
      (node (ref "IO1") (pin "3") (pinfunction "ADECAY_3") (pintype "bidirectional"))
      (node (ref "IO1") (pin "5") (pinfunction "AISEN_5") (pintype "bidirectional"))
      (node (ref "IO1") (pin "8") (pinfunction "BISEN_8") (pintype "bidirectional"))
      (node (ref "IO1") (pin "PAD") (pinfunction "GND_PAD_PAD") (pintype "bidirectional"))
      (node (ref "IR_S_LEFT") (pin "A") (pinfunction "A_A") (pintype "passive"))
      (node (ref "IR_S_RIGHT") (pin "A") (pinfunction "A_A") (pintype "passive"))
      (node (ref "JP1") (pin "1") (pinfunction "1_1") (pintype "passive"))
      (node (ref "LASER") (pin "3") (pinfunction "3_3") (pintype "passive"))
      (node (ref "LASER1") (pin "3") (pinfunction "3_3") (pintype "passive"))
      (node (ref "LED11") (pin "C") (pinfunction "C_C") (pintype "passive"))
      (node (ref "LED12") (pin "C") (pinfunction "C_C") (pintype "passive"))
      (node (ref "LED9") (pin "A") (pinfunction "A_A") (pintype "passive"))
      (node (ref "LSM6DS0") (pin "P$10") (pinfunction "RES2_P$10") (pintype "bidirectional"))
      (node (ref "LSM6DS0") (pin "P$11") (pinfunction "RES3_P$11") (pintype "bidirectional"))
      (node (ref "LSM6DS0") (pin "P$12") (pinfunction "GND_P$12") (pintype "power_in"))
      (node (ref "LSM6DS0") (pin "P$13") (pinfunction "GND_P$13") (pintype "power_in"))
      (node (ref "LSM6DS0") (pin "P$15") (pinfunction "RES4_P$15") (pintype "bidirectional"))
      (node (ref "LSM6DS0") (pin "P$4") (pinfunction "SDO_P$4") (pintype "bidirectional"))
      (node (ref "LSM6DS0") (pin "P$8") (pinfunction "DEN_P$8") (pintype "bidirectional"))
      (node (ref "LSM6DS0") (pin "P$9") (pinfunction "RES1_P$9") (pintype "bidirectional"))
      (node (ref "Q2") (pin "2") (pinfunction "S_2") (pintype "passive"))
      (node (ref "Q3") (pin "2") (pinfunction "S_2") (pintype "passive"))
      (node (ref "R3") (pin "1") (pinfunction "1_1") (pintype "passive"))
      (node (ref "R30") (pin "1") (pinfunction "1_1") (pintype "passive"))
      (node (ref "R4") (pin "2") (pinfunction "2_2") (pintype "passive"))
      (node (ref "RESET") (pin "1") (pinfunction "1_1") (pintype "passive"))
      (node (ref "RESET") (pin "2") (pinfunction "2_2") (pintype "passive"))
      (node (ref "SV1") (pin "4") (pinfunction "4_4") (pintype "passive"))
      (node (ref "TP2") (pin "TP") (pinfunction "TP_TP") (pintype "input"))
      (node (ref "U$10") (pin "P$2") (pinfunction "C_P$2") (pintype "bidirectional"))
      (node (ref "U$11") (pin "P$6") (pinfunction "GND_P$6") (pintype "bidirectional"))
      (node (ref "U$12") (pin "P$6") (pinfunction "GND_P$6") (pintype "bidirectional"))
      (node (ref "U$3") (pin "P$2") (pinfunction "C_P$2") (pintype "bidirectional"))
      (node (ref "U$4") (pin "P$2") (pinfunction "C_P$2") (pintype "bidirectional"))
      (node (ref "U$5") (pin "P$2") (pinfunction "C_P$2") (pintype "bidirectional"))
      (node (ref "U$6") (pin "P$2") (pinfunction "C_P$2") (pintype "bidirectional"))
      (node (ref "U$7") (pin "P$2") (pinfunction "C_P$2") (pintype "bidirectional"))
      (node (ref "U$8") (pin "P$2") (pinfunction "C_P$2") (pintype "bidirectional"))
      (node (ref "U$9") (pin "P$2") (pinfunction "C_P$2") (pintype "bidirectional"))
      (node (ref "U1") (pin "12") (pinfunction "GND_12") (pintype "bidirectional"))
      (node (ref "U1") (pin "2") (pinfunction "GND_2") (pintype "bidirectional"))
      (node (ref "U1") (pin "3") (pinfunction "GND_3") (pintype "bidirectional"))
      (node (ref "U1") (pin "4") (pinfunction "GND_4") (pintype "bidirectional"))
      (node (ref "U1") (pin "6") (pinfunction "GND_6") (pintype "bidirectional"))
      (node (ref "U4") (pin "12") (pinfunction "VSSA/VREF-_12") (pintype "power_in"))
      (node (ref "U4") (pin "28") (pinfunction "PB2_28") (pintype "bidirectional"))
      (node (ref "U4") (pin "31") (pinfunction "VSS_2_31") (pintype "passive"))
      (node (ref "U4") (pin "47") (pinfunction "VSS_3_47") (pintype "passive"))
      (node (ref "U4") (pin "63") (pinfunction "VSS_1_63") (pintype "passive"))
      (node (ref "USER") (pin "1") (pinfunction "1_1") (pintype "passive"))
      (node (ref "USER") (pin "2") (pinfunction "2_2") (pintype "passive"))
      (node (ref "X1") (pin "5") (pinfunction "5_5") (pintype "passive"))
    )
    (net (code "43") (name "Net-(C16-Pad1)") (class "Default")
      (node (ref "C16") (pin "1") (pinfunction "1_1") (pintype "passive"))
      (node (ref "R8") (pin "1") (pinfunction "1_1") (pintype "passive"))
      (node (ref "X1") (pin "3") (pinfunction "3_3") (pintype "passive"))
    )
    (net (code "44") (name "Net-(C17-Pad2)") (class "Default")
      (node (ref "C17") (pin "2") (pinfunction "2_2") (pintype "passive"))
      (node (ref "C18") (pin "2") (pinfunction "2_2") (pintype "passive"))
      (node (ref "LASER1") (pin "4") (pinfunction "4_4") (pintype "passive"))
      (node (ref "R35") (pin "2") (pinfunction "2_2") (pintype "passive"))
      (node (ref "U1") (pin "1") (pinfunction "VCC_1") (pintype "bidirectional"))
      (node (ref "U1") (pin "11") (pinfunction "VCC_11") (pintype "bidirectional"))
    )
    (net (code "45") (name "Net-(C20-Pad2)") (class "Default")
      (node (ref "C20") (pin "2") (pinfunction "2_2") (pintype "passive"))
      (node (ref "R7") (pin "1") (pinfunction "1_1") (pintype "passive"))
      (node (ref "X1") (pin "2") (pinfunction "2_2") (pintype "passive"))
    )
    (net (code "46") (name "Net-(D1-PadA)") (class "Default")
      (node (ref "D1") (pin "A") (pinfunction "A_A") (pintype "passive"))
      (node (ref "X1") (pin "1") (pinfunction "1_1") (pintype "passive"))
    )
    (net (code "47") (name "Net-(IO1-AOUT1)") (class "Default")
      (node (ref "IO1") (pin "4") (pinfunction "AOUT1_4") (pintype "bidirectional"))
      (node (ref "U$12") (pin "P$1") (pinfunction "P$1_P$1") (pintype "bidirectional"))
    )
    (net (code "48") (name "Net-(IO1-AOUT2)") (class "Default")
      (node (ref "IO1") (pin "6") (pinfunction "AOUT2_6") (pintype "bidirectional"))
      (node (ref "U$12") (pin "P$2") (pinfunction "P$2_P$2") (pintype "bidirectional"))
    )
    (net (code "49") (name "Net-(IO1-AVREF)") (class "Default")
      (node (ref "IO1") (pin "22") (pinfunction "AVREF_22") (pintype "bidirectional"))
      (node (ref "IO1") (pin "23") (pinfunction "BVREF_23") (pintype "bidirectional"))
      (node (ref "IO1") (pin "24") (pinfunction "VREFO_24") (pintype "bidirectional"))
    )
    (net (code "50") (name "Net-(IO1-BOUT1)") (class "Default")
      (node (ref "IO1") (pin "9") (pinfunction "BOUT1_9") (pintype "bidirectional"))
      (node (ref "U$11") (pin "P$2") (pinfunction "P$2_P$2") (pintype "bidirectional"))
    )
    (net (code "51") (name "Net-(IO1-BOUT2)") (class "Default")
      (node (ref "IO1") (pin "7") (pinfunction "BOUT2_7") (pintype "bidirectional"))
      (node (ref "U$11") (pin "P$1") (pinfunction "P$1_P$1") (pintype "bidirectional"))
    )
    (net (code "52") (name "Net-(IO1-NSLEEP)") (class "Default")
      (node (ref "IO1") (pin "1") (pinfunction "NSLEEP_1") (pintype "bidirectional"))
      (node (ref "R1") (pin "2") (pinfunction "2_2") (pintype "passive"))
    )
    (net (code "53") (name "Net-(IO1-VCP)") (class "Default")
      (node (ref "C3") (pin "2") (pinfunction "2_2") (pintype "passive"))
      (node (ref "IO1") (pin "17") (pinfunction "VCP_17") (pintype "bidirectional"))
    )
    (net (code "54") (name "Net-(IO1-VINT)") (class "Default")
      (node (ref "C4") (pin "2") (pinfunction "2_2") (pintype "passive"))
      (node (ref "IO1") (pin "20") (pinfunction "VINT_20") (pintype "bidirectional"))
    )
    (net (code "55") (name "Net-(IR_LEFT-PadA)") (class "Default")
      (node (ref "IR_LEFT") (pin "A") (pinfunction "A_A") (pintype "passive"))
      (node (ref "R33") (pin "1") (pinfunction "1_1") (pintype "passive"))
    )
    (net (code "56") (name "Net-(IR_RIGHT-PadA)") (class "Default")
      (node (ref "IR_RIGHT") (pin "A") (pinfunction "A_A") (pintype "passive"))
      (node (ref "R31") (pin "1") (pinfunction "1_1") (pintype "passive"))
    )
    (net (code "57") (name "Net-(LED1-PadA)") (class "Default")
      (node (ref "LED1") (pin "A") (pinfunction "A_A") (pintype "passive"))
      (node (ref "R5") (pin "1") (pinfunction "1_1") (pintype "passive"))
    )
    (net (code "58") (name "Net-(LED2-PadA)") (class "Default")
      (node (ref "LED2") (pin "A") (pinfunction "A_A") (pintype "passive"))
      (node (ref "R10") (pin "1") (pinfunction "1_1") (pintype "passive"))
    )
    (net (code "59") (name "Net-(LED3-PadA)") (class "Default")
      (node (ref "LED3") (pin "A") (pinfunction "A_A") (pintype "passive"))
      (node (ref "R12") (pin "1") (pinfunction "1_1") (pintype "passive"))
    )
    (net (code "60") (name "Net-(LED4-PadA)") (class "Default")
      (node (ref "LED4") (pin "A") (pinfunction "A_A") (pintype "passive"))
      (node (ref "R17") (pin "1") (pinfunction "1_1") (pintype "passive"))
    )
    (net (code "61") (name "Net-(LED5-PadA)") (class "Default")
      (node (ref "LED5") (pin "A") (pinfunction "A_A") (pintype "passive"))
      (node (ref "R19") (pin "1") (pinfunction "1_1") (pintype "passive"))
    )
    (net (code "62") (name "Net-(LED6-PadA)") (class "Default")
      (node (ref "LED6") (pin "A") (pinfunction "A_A") (pintype "passive"))
      (node (ref "R21") (pin "1") (pinfunction "1_1") (pintype "passive"))
    )
    (net (code "63") (name "Net-(LED7-PadA)") (class "Default")
      (node (ref "LED7") (pin "A") (pinfunction "A_A") (pintype "passive"))
      (node (ref "R23") (pin "1") (pinfunction "1_1") (pintype "passive"))
    )
    (net (code "64") (name "Net-(LED8-PadA)") (class "Default")
      (node (ref "LED8") (pin "A") (pinfunction "A_A") (pintype "passive"))
      (node (ref "R25") (pin "1") (pinfunction "1_1") (pintype "passive"))
    )
    (net (code "65") (name "Net-(LED10-PadA)") (class "Default")
      (node (ref "LED10") (pin "A") (pinfunction "A_A") (pintype "passive"))
      (node (ref "R29") (pin "1") (pinfunction "1_1") (pintype "passive"))
    )
    (net (code "66") (name "Net-(LED11-PadA)") (class "Default")
      (node (ref "LED11") (pin "A") (pinfunction "A_A") (pintype "passive"))
      (node (ref "R28") (pin "1") (pinfunction "1_1") (pintype "passive"))
    )
    (net (code "67") (name "Net-(LED12-PadA)") (class "Default")
      (node (ref "LED12") (pin "A") (pinfunction "A_A") (pintype "passive"))
      (node (ref "R27") (pin "2") (pinfunction "2_2") (pintype "passive"))
    )
    (net (code "68") (name "Net-(LSM6DS0-CAP)") (class "Default")
      (node (ref "C14") (pin "2") (pinfunction "2_2") (pintype "passive"))
      (node (ref "LSM6DS0") (pin "P$14") (pinfunction "CAP_P$14") (pintype "bidirectional"))
    )
    (net (code "69") (name "Net-(U1-SCL)") (class "Default")
      (node (ref "LASER1") (pin "2") (pinfunction "2_2") (pintype "passive"))
      (node (ref "U1") (pin "10") (pinfunction "SCL_10") (pintype "bidirectional"))
    )
    (net (code "70") (name "Net-(U1-SDA)") (class "Default")
      (node (ref "LASER1") (pin "1") (pinfunction "1_1") (pintype "passive"))
      (node (ref "U1") (pin "9") (pinfunction "SDA_9") (pintype "bidirectional"))
    )
    (net (code "71") (name "Net-(U1-~{SHUT})") (class "Default")
      (node (ref "R35") (pin "1") (pinfunction "1_1") (pintype "passive"))
      (node (ref "U1") (pin "5") (pinfunction "~{SHUT}_5") (pintype "bidirectional"))
    )
    (net (code "72") (name "VCC") (class "Default")
      (node (ref "C1") (pin "1") (pinfunction "1_1") (pintype "passive"))
      (node (ref "C10") (pin "1") (pinfunction "1_1") (pintype "passive"))
      (node (ref "C2") (pin "1") (pinfunction "1_1") (pintype "passive"))
      (node (ref "C3") (pin "1") (pinfunction "1_1") (pintype "passive"))
      (node (ref "C7") (pin "+") (pinfunction "+_+") (pintype "passive"))
      (node (ref "C9") (pin "1") (pinfunction "1_1") (pintype "passive"))
      (node (ref "D1") (pin "C") (pinfunction "C_C") (pintype "passive"))
      (node (ref "IC2") (pin "1") (pinfunction "VI_1") (pintype "input"))
      (node (ref "IO1") (pin "18") (pinfunction "VM_18") (pintype "bidirectional"))
      (node (ref "IO1") (pin "19") (pinfunction "VM1_19") (pintype "bidirectional"))
      (node (ref "JP1") (pin "2") (pinfunction "2_2") (pintype "passive"))
      (node (ref "R1") (pin "1") (pinfunction "1_1") (pintype "passive"))
    )
    (net (code "73") (name "unconnected-(IO1-NFAULT-Pad16)") (class "Default")
      (node (ref "IO1") (pin "16") (pinfunction "NFAULT_16") (pintype "bidirectional"))
    )
    (net (code "74") (name "unconnected-(LSM6DS0-DRDY{slash}INT2-PadP$6)") (class "Default")
      (node (ref "LSM6DS0") (pin "P$6") (pinfunction "DRDY/INT2_P$6") (pintype "bidirectional"))
    )
    (net (code "75") (name "unconnected-(LSM6DS0-INT1-PadP$7)") (class "Default")
      (node (ref "LSM6DS0") (pin "P$7") (pinfunction "INT1_P$7") (pintype "bidirectional"))
    )
    (net (code "76") (name "unconnected-(U1-~{INT}-Pad7)") (class "Default")
      (node (ref "U1") (pin "7") (pinfunction "~{INT}_7") (pintype "bidirectional"))
    )
    (net (code "77") (name "unconnected-(U4A-PB10-Pad29)") (class "Default")
      (node (ref "U4") (pin "29") (pinfunction "PB10_29") (pintype "bidirectional"))
    )
    (net (code "78") (name "unconnected-(U4A-PB11-Pad30)") (class "Default")
      (node (ref "U4") (pin "30") (pinfunction "PB11_30") (pintype "bidirectional"))
    )
    (net (code "79") (name "unconnected-(U4A-PC1-Pad9)") (class "Default")
      (node (ref "U4") (pin "9") (pinfunction "PC1_9") (pintype "bidirectional"))
    )
    (net (code "80") (name "unconnected-(U4A-PC2-Pad10)") (class "Default")
      (node (ref "U4") (pin "10") (pinfunction "PC2_10") (pintype "bidirectional"))
    )
    (net (code "81") (name "unconnected-(U4A-PC3-Pad11)") (class "Default")
      (node (ref "U4") (pin "11") (pinfunction "PC3_11") (pintype "bidirectional"))
    )
    (net (code "82") (name "unconnected-(U4A-PC4-Pad24)") (class "Default")
      (node (ref "U4") (pin "24") (pinfunction "PC4_24") (pintype "bidirectional"))
    )
    (net (code "83") (name "unconnected-(U4A-PC5-Pad25)") (class "Default")
      (node (ref "U4") (pin "25") (pinfunction "PC5_25") (pintype "bidirectional"))
    )
    (net (code "84") (name "unconnected-(U4A-PC14-OSC32_IN-Pad3)") (class "Default")
      (node (ref "U4") (pin "3") (pinfunction "PC14-OSC32_IN_3") (pintype "bidirectional"))
    )
    (net (code "85") (name "unconnected-(U4A-PC15-OSC32_OUT-Pad4)") (class "Default")
      (node (ref "U4") (pin "4") (pinfunction "PC15-OSC32_OUT_4") (pintype "bidirectional"))
    )
    (net (code "86") (name "unconnected-(U4A-PF4-Pad18)") (class "Default")
      (node (ref "U4") (pin "18") (pinfunction "PF4_18") (pintype "bidirectional"))
    )
    (net (code "87") (name "unconnected-(U4B-PB3-Pad55)") (class "Default")
      (node (ref "U4") (pin "55") (pinfunction "PB3_55") (pintype "bidirectional"))
    )
    (net (code "88") (name "unconnected-(U4B-PB8-Pad61)") (class "Default")
      (node (ref "U4") (pin "61") (pinfunction "PB8_61") (pintype "bidirectional"))
    )
    (net (code "89") (name "unconnected-(U4B-PB9-Pad62)") (class "Default")
      (node (ref "U4") (pin "62") (pinfunction "PB9_62") (pintype "bidirectional"))
    )
    (net (code "90") (name "unconnected-(U4B-PC8-Pad39)") (class "Default")
      (node (ref "U4") (pin "39") (pinfunction "PC8_39") (pintype "bidirectional"))
    )
    (net (code "91") (name "unconnected-(U4B-PC9-Pad40)") (class "Default")
      (node (ref "U4") (pin "40") (pinfunction "PC9_40") (pintype "bidirectional"))
    )
    (net (code "92") (name "unconnected-(U4B-PC10-Pad51)") (class "Default")
      (node (ref "U4") (pin "51") (pinfunction "PC10_51") (pintype "bidirectional"))
    )
    (net (code "93") (name "unconnected-(U4B-PD2-Pad54)") (class "Default")
      (node (ref "U4") (pin "54") (pinfunction "PD2_54") (pintype "bidirectional"))
    )
    (net (code "94") (name "unconnected-(USER-Pad4)") (class "Default")
      (node (ref "USER") (pin "4") (pinfunction "4_4") (pintype "passive"))
    )
    (net (code "95") (name "unconnected-(X1-Pad4)") (class "Default")
      (node (ref "X1") (pin "4") (pinfunction "4_4") (pintype "passive"))
    )
  )
)
